# LCL.net
KiCad netlist of a schematic drawn in Altium Designer
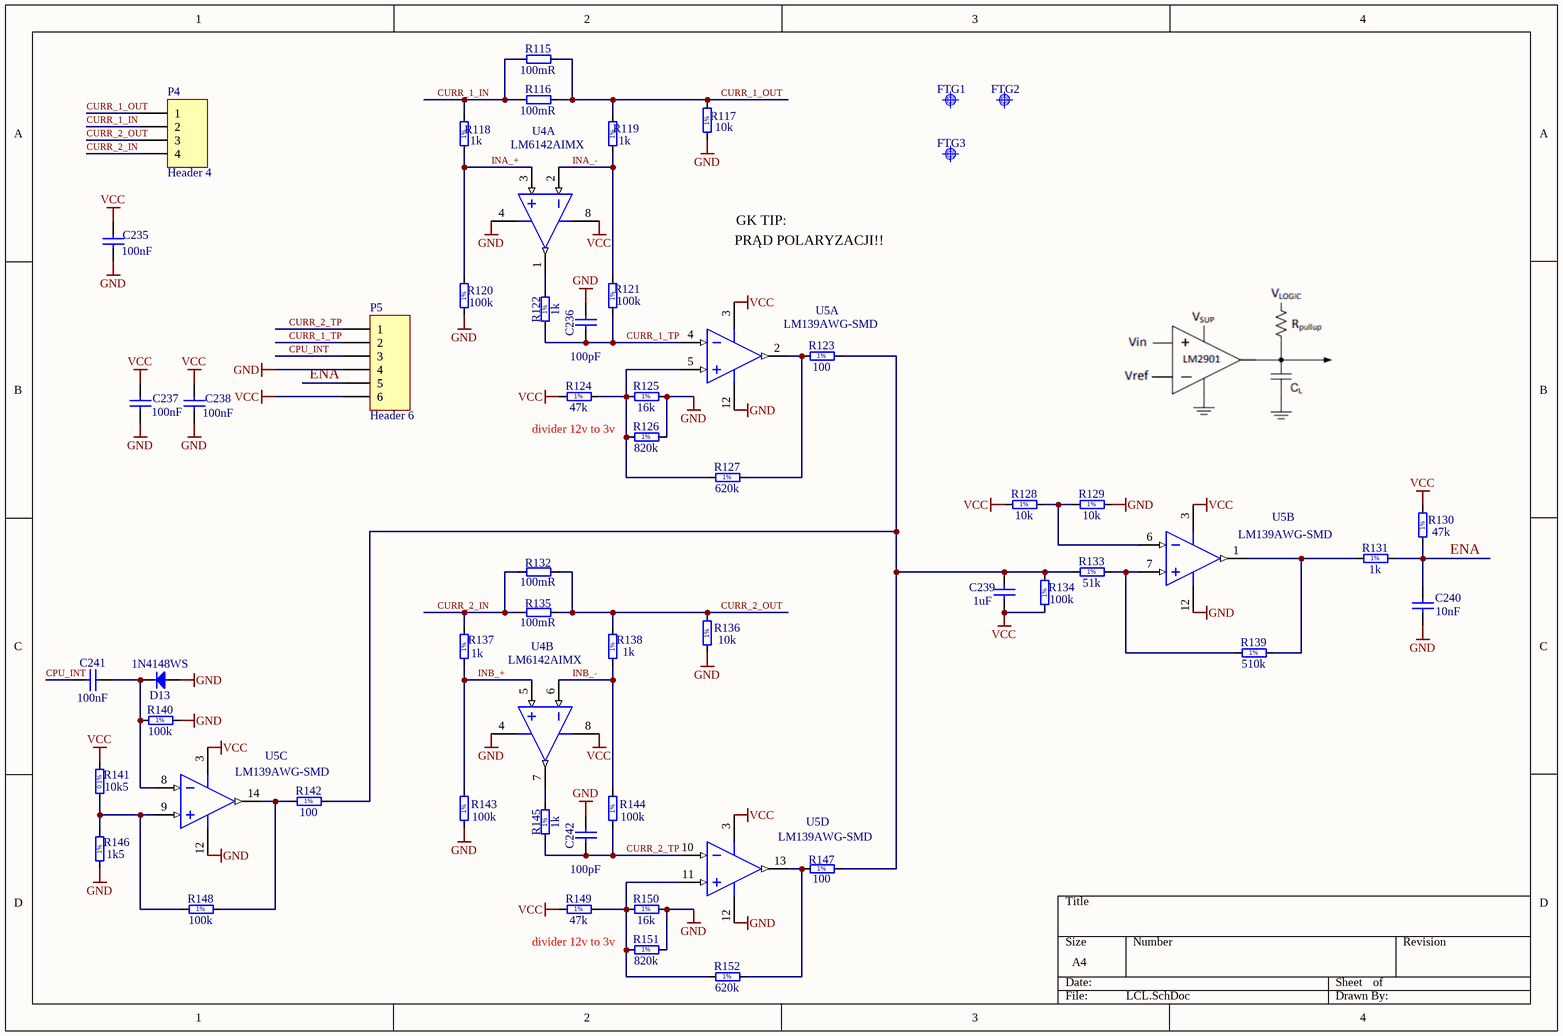
[diagram p0: LCL.SchDoc]

(export (version "E")
  (design (tool "Eeschema 10.0.6"))
  (components
    (comp (ref "C235")
      (value "100nF")
      (footprint "CAPC1608X87N")
      (description "Non-polarised capacitor")
      (fields
        (field (name "PART NUMBER") "CC0603_100NF_50V_10%_X7R")
        (field (name "VOLTAGE") "50V")
        (field (name "AUTHOR") "CERN DEM JLC")
      )
      (libsource (lib "Capacitors") (part "Capacitor - non polarized"))
    )
    (comp (ref "C236")
      (value "100pF")
      (footprint "CAPC1608X87N")
      (description "Non-polarised capacitor")
      (fields
        (field (name "PART NUMBER") "CC0603_100PF_50V_10%_X7R")
        (field (name "VOLTAGE") "50V")
        (field (name "AUTHOR") "CERN DEM JLC")
      )
      (libsource (lib "Capacitors") (part "Capacitor - non polarized"))
    )
    (comp (ref "C237")
      (value "100nF")
      (footprint "CAPC1608X87N")
      (description "Non-polarised capacitor")
      (fields
        (field (name "PART NUMBER") "CC0603_100NF_50V_10%_X7R")
        (field (name "VOLTAGE") "50V")
        (field (name "AUTHOR") "CERN DEM JLC")
      )
      (libsource (lib "Capacitors") (part "Capacitor - non polarized"))
    )
    (comp (ref "C238")
      (value "100nF")
      (footprint "CAPC1608X87N")
      (description "Non-polarised capacitor")
      (fields
        (field (name "PART NUMBER") "CC0603_100NF_50V_10%_X7R")
        (field (name "VOLTAGE") "50V")
        (field (name "AUTHOR") "CERN DEM JLC")
      )
      (libsource (lib "Capacitors") (part "Capacitor - non polarized"))
    )
    (comp (ref "C239")
      (value "1uF")
      (footprint "CAPC1608X87N")
      (description "Non-polarised capacitor")
      (fields
        (field (name "PART NUMBER") "CC0603_1UF_25V_10%_X7R")
        (field (name "VOLTAGE") "25V")
        (field (name "AUTHOR") "CERN DEM JLC")
      )
      (libsource (lib "Capacitors") (part "Capacitor - non polarized"))
    )
    (comp (ref "C240")
      (value "10nF")
      (footprint "CAPC1608X87N")
      (description "Non-polarised capacitor")
      (fields
        (field (name "PART NUMBER") "CC0603_10NF_50V_10%_X7R")
        (field (name "VOLTAGE") "50V")
        (field (name "AUTHOR") "CERN DEM JLC")
      )
      (libsource (lib "Capacitors") (part "Capacitor - non polarized"))
    )
    (comp (ref "C241")
      (value "100nF")
      (footprint "CAPC1608X87N")
      (description "Non-polarised capacitor")
      (fields
        (field (name "PART NUMBER") "CC0603_100NF_50V_10%_X7R")
        (field (name "VOLTAGE") "50V")
        (field (name "AUTHOR") "CERN DEM JLC")
      )
      (libsource (lib "Capacitors") (part "Capacitor - non polarized"))
    )
    (comp (ref "C242")
      (value "100pF")
      (footprint "CAPC1608X87N")
      (description "Non-polarised capacitor")
      (fields
        (field (name "PART NUMBER") "CC0603_100PF_50V_10%_X7R")
        (field (name "VOLTAGE") "50V")
        (field (name "AUTHOR") "CERN DEM JLC")
      )
      (libsource (lib "Capacitors") (part "Capacitor - non polarized"))
    )
    (comp (ref "D13")
      (value "1N4148WS")
      (footprint "SODFL2512X100N")
      (description "Diode")
      (fields
        (field (name "VOLTAGE") "75V")
        (field (name "POWER") "150mA")
        (field (name "AUTHOR") "CERN DEM JLC")
      )
      (libsource (lib "ICs And Semiconductors") (part "Diode"))
    )
    (comp (ref "FTG1")
      (value "Use only in PCB")
      (footprint "FIDUCIAL_TOP_C100-200")
      (description "Fiducial Target")
      (fields (field (name "PART NUMBER") "FIDUCIAL_TARGET_C100-200") (field (name "AUTHOR") "CERN DEM JLC"))
      (libsource (lib "Eletro-mechanical") (part "Fiducial Target"))
    )
    (comp (ref "FTG2")
      (value "Use only in PCB")
      (footprint "FIDUCIAL_TOP_C100-200")
      (description "Fiducial Target")
      (fields (field (name "PART NUMBER") "FIDUCIAL_TARGET_C100-200") (field (name "AUTHOR") "CERN DEM JLC"))
      (libsource (lib "Eletro-mechanical") (part "Fiducial Target"))
    )
    (comp (ref "FTG3")
      (value "Use only in PCB")
      (footprint "FIDUCIAL_TOP_C100-200")
      (description "Fiducial Target")
      (fields (field (name "PART NUMBER") "FIDUCIAL_TARGET_C100-200") (field (name "AUTHOR") "CERN DEM JLC"))
      (libsource (lib "Eletro-mechanical") (part "Fiducial Target"))
    )
    (comp (ref "P4")
      (value "Header 4")
      (footprint "1x4 Header 2mm male")
      (description "Header, 4-Pin")
      (fields (field (name "PUBLISHER") "Altium Limited"))
      (libsource (lib "Connectors-headers") (part "Header 4"))
    )
    (comp (ref "P5")
      (value "Header 6")
      (footprint "2x3 Header 2mm male")
      (description "Header, 6-Pin")
      (fields (field (name "PUBLISHER") "Altium Limited"))
      (libsource (lib "Connectors-headers") (part "Header 6"))
    )
    (comp (ref "R115")
      (value "100mR")
      (footprint "RESC1608X55N")
      (description "Resistor")
      (fields
        (field (name "PART NUMBER") "100mR 0603")
        (field (name "MANUFACTURER") "GENERIC")
        (field (name "AUTHOR") "CERN DEM JLC")
      )
      (libsource (lib "Resistors") (part "Resistor"))
    )
    (comp (ref "R116")
      (value "100mR")
      (footprint "RESC1608X55N")
      (description "Resistor")
      (fields
        (field (name "PART NUMBER") "100mR 0603")
        (field (name "MANUFACTURER") "GENERIC")
        (field (name "AUTHOR") "CERN DEM JLC")
      )
      (libsource (lib "Resistors") (part "Resistor"))
    )
    (comp (ref "R117")
      (value "10k")
      (footprint "RESC1608X55N")
      (description "Resistor - 1%")
      (fields
        (field (name "PART NUMBER") "R0603_10K_1%_0.1W_100PPM")
        (field (name "POWER") "0.1W")
        (field (name "AUTHOR") "CERN DEM JLC")
      )
      (libsource (lib "Resistors") (part "Resistor - 1%"))
    )
    (comp (ref "R118")
      (value "1k")
      (footprint "RESC1608X55N")
      (description "Resistor - 1%")
      (fields
        (field (name "PART NUMBER") "R0603_1K_1%_0.1W_100PPM")
        (field (name "POWER") "0.1W")
        (field (name "AUTHOR") "CERN DEM JLC")
      )
      (libsource (lib "Resistors") (part "Resistor - 1%"))
    )
    (comp (ref "R119")
      (value "1k")
      (footprint "RESC1608X55N")
      (description "Resistor - 1%")
      (fields
        (field (name "PART NUMBER") "R0603_1K_1%_0.1W_100PPM")
        (field (name "POWER") "0.1W")
        (field (name "AUTHOR") "CERN DEM JLC")
      )
      (libsource (lib "Resistors") (part "Resistor - 1%"))
    )
    (comp (ref "R120")
      (value "100k")
      (footprint "RESC1608X55N")
      (description "Resistor - 1%")
      (fields
        (field (name "PART NUMBER") "R0603_100K_1%_0.1W_100PPM")
        (field (name "POWER") "0.1W")
        (field (name "AUTHOR") "CERN DEM JLC")
      )
      (libsource (lib "Resistors") (part "Resistor - 1%"))
    )
    (comp (ref "R121")
      (value "100k")
      (footprint "RESC1608X55N")
      (description "Resistor - 1%")
      (fields
        (field (name "PART NUMBER") "R0603_100K_1%_0.1W_100PPM")
        (field (name "POWER") "0.1W")
        (field (name "AUTHOR") "CERN DEM JLC")
      )
      (libsource (lib "Resistors") (part "Resistor - 1%"))
    )
    (comp (ref "R122")
      (value "1k")
      (footprint "RESC1608X55N")
      (description "Resistor - 1%")
      (fields
        (field (name "PART NUMBER") "R0603_1K_1%_0.1W_100PPM")
        (field (name "POWER") "0.1W")
        (field (name "AUTHOR") "CERN DEM JLC")
      )
      (libsource (lib "Resistors") (part "Resistor - 1%"))
    )
    (comp (ref "R123")
      (value "100")
      (footprint "RESC1608X55N")
      (description "Resistor - 1%")
      (fields
        (field (name "PART NUMBER") "R0603_100R_1%_0.1W_100PPM")
        (field (name "POWER") "0.1W")
        (field (name "AUTHOR") "CERN DEM JLC")
      )
      (libsource (lib "Resistors") (part "Resistor - 1%"))
    )
    (comp (ref "R124")
      (value "47k")
      (footprint "RESC1608X55N")
      (description "Resistor - 1%")
      (fields
        (field (name "PART NUMBER") "R0603_47K_1%_0.1W_100PPM")
        (field (name "POWER") "0.1W")
        (field (name "AUTHOR") "CERN DEM JLC")
      )
      (libsource (lib "Resistors") (part "Resistor - 1%"))
    )
    (comp (ref "R125")
      (value "16k")
      (footprint "RESC1608X55N")
      (description "Resistor - 1%")
      (fields
        (field (name "PART NUMBER") "R0603_16K_1%_0.1W_100PPM")
        (field (name "POWER") "0.1W")
        (field (name "AUTHOR") "CERN DEM JLC")
      )
      (libsource (lib "Resistors") (part "Resistor - 1%"))
    )
    (comp (ref "R126")
      (value "820k")
      (footprint "RESC1608X55N")
      (description "Resistor - 1%")
      (fields
        (field (name "PART NUMBER") "R0603_820K_1%_0.1W_100PPM")
        (field (name "POWER") "0.1W")
        (field (name "AUTHOR") "CERN DEM JLC")
      )
      (libsource (lib "Resistors") (part "Resistor - 1%"))
    )
    (comp (ref "R127")
      (value "620k")
      (footprint "RESC1608X55N")
      (description "Resistor - 1%")
      (fields
        (field (name "PART NUMBER") "R0603_620K_1%_0.1W_100PPM")
        (field (name "POWER") "0.1W")
        (field (name "AUTHOR") "CERN DEM JLC")
      )
      (libsource (lib "Resistors") (part "Resistor - 1%"))
    )
    (comp (ref "R128")
      (value "10k")
      (footprint "RESC1608X55N")
      (description "Resistor - 1%")
      (fields
        (field (name "PART NUMBER") "R0603_10K_1%_0.1W_100PPM")
        (field (name "POWER") "0.1W")
        (field (name "AUTHOR") "CERN DEM JLC")
      )
      (libsource (lib "Resistors") (part "Resistor - 1%"))
    )
    (comp (ref "R129")
      (value "10k")
      (footprint "RESC1608X55N")
      (description "Resistor - 1%")
      (fields
        (field (name "PART NUMBER") "R0603_10K_1%_0.1W_100PPM")
        (field (name "POWER") "0.1W")
        (field (name "AUTHOR") "CERN DEM JLC")
      )
      (libsource (lib "Resistors") (part "Resistor - 1%"))
    )
    (comp (ref "R130")
      (value "47k")
      (footprint "RESC1608X55N")
      (description "Resistor - 1%")
      (fields
        (field (name "PART NUMBER") "R0603_47K_1%_0.1W_100PPM")
        (field (name "POWER") "0.1W")
        (field (name "AUTHOR") "CERN DEM JLC")
      )
      (libsource (lib "Resistors") (part "Resistor - 1%"))
    )
    (comp (ref "R131")
      (value "1k")
      (footprint "RESC1608X55N")
      (description "Resistor - 1%")
      (fields
        (field (name "PART NUMBER") "R0603_1K_1%_0.1W_100PPM")
        (field (name "POWER") "0.1W")
        (field (name "AUTHOR") "CERN DEM JLC")
      )
      (libsource (lib "Resistors") (part "Resistor - 1%"))
    )
    (comp (ref "R132")
      (value "100mR")
      (footprint "RESC1608X55N")
      (description "Resistor")
      (fields
        (field (name "PART NUMBER") "100mR 0603")
        (field (name "MANUFACTURER") "GENERIC")
        (field (name "AUTHOR") "CERN DEM JLC")
      )
      (libsource (lib "Resistors") (part "Resistor"))
    )
    (comp (ref "R133")
      (value "51k")
      (footprint "RESC1608X55N")
      (description "Resistor - 1%")
      (fields
        (field (name "PART NUMBER") "R0603_51K_1%_0.1W_100PPM")
        (field (name "POWER") "0.1W")
        (field (name "AUTHOR") "CERN DEM JLC")
      )
      (libsource (lib "Resistors") (part "Resistor - 1%"))
    )
    (comp (ref "R134")
      (value "100k")
      (footprint "RESC1608X55N")
      (description "Resistor - 1%")
      (fields
        (field (name "PART NUMBER") "R0603_100K_1%_0.1W_100PPM")
        (field (name "POWER") "0.1W")
        (field (name "AUTHOR") "CERN DEM JLC")
      )
      (libsource (lib "Resistors") (part "Resistor - 1%"))
    )
    (comp (ref "R135")
      (value "100mR")
      (footprint "RESC1608X55N")
      (description "Resistor")
      (fields
        (field (name "PART NUMBER") "100mR 0603")
        (field (name "MANUFACTURER") "GENERIC")
        (field (name "AUTHOR") "CERN DEM JLC")
      )
      (libsource (lib "Resistors") (part "Resistor"))
    )
    (comp (ref "R136")
      (value "10k")
      (footprint "RESC1608X55N")
      (description "Resistor - 1%")
      (fields
        (field (name "PART NUMBER") "R0603_10K_1%_0.1W_100PPM")
        (field (name "POWER") "0.1W")
        (field (name "AUTHOR") "CERN DEM JLC")
      )
      (libsource (lib "Resistors") (part "Resistor - 1%"))
    )
    (comp (ref "R137")
      (value "1k")
      (footprint "RESC1608X55N")
      (description "Resistor - 1%")
      (fields
        (field (name "PART NUMBER") "R0603_1K_1%_0.1W_100PPM")
        (field (name "POWER") "0.1W")
        (field (name "AUTHOR") "CERN DEM JLC")
      )
      (libsource (lib "Resistors") (part "Resistor - 1%"))
    )
    (comp (ref "R138")
      (value "1k")
      (footprint "RESC1608X55N")
      (description "Resistor - 1%")
      (fields
        (field (name "PART NUMBER") "R0603_1K_1%_0.1W_100PPM")
        (field (name "POWER") "0.1W")
        (field (name "AUTHOR") "CERN DEM JLC")
      )
      (libsource (lib "Resistors") (part "Resistor - 1%"))
    )
    (comp (ref "R139")
      (value "510k")
      (footprint "RESC1608X55N")
      (description "Resistor - 1%")
      (fields
        (field (name "PART NUMBER") "R0603_510K_1%_0.1W_100PPM")
        (field (name "POWER") "0.1W")
        (field (name "AUTHOR") "CERN DEM JLC")
      )
      (libsource (lib "Resistors") (part "Resistor - 1%"))
    )
    (comp (ref "R140")
      (value "100k")
      (footprint "RESC1608X55N")
      (description "Resistor - 1%")
      (fields
        (field (name "PART NUMBER") "R0603_100K_1%_0.1W_100PPM")
        (field (name "POWER") "0.1W")
        (field (name "AUTHOR") "CERN DEM JLC")
      )
      (libsource (lib "Resistors") (part "Resistor - 1%"))
    )
    (comp (ref "R141")
      (value "10k5")
      (footprint "RESC1608X55N")
      (description "Resistor - 0.1%")
      (fields
        (field (name "PART NUMBER") "R0603_10K5_0.1%_0.063W_10PPM")
        (field (name "POWER") "0.063W")
        (field (name "AUTHOR") "CERN DEM JLC")
      )
      (libsource (lib "Resistors") (part "Resistor - 0.1%"))
    )
    (comp (ref "R142")
      (value "100")
      (footprint "RESC1608X55N")
      (description "Resistor - 1%")
      (fields
        (field (name "PART NUMBER") "R0603_100R_1%_0.1W_100PPM")
        (field (name "POWER") "0.1W")
        (field (name "AUTHOR") "CERN DEM JLC")
      )
      (libsource (lib "Resistors") (part "Resistor - 1%"))
    )
    (comp (ref "R143")
      (value "100k")
      (footprint "RESC1608X55N")
      (description "Resistor - 1%")
      (fields
        (field (name "PART NUMBER") "R0603_100K_1%_0.1W_100PPM")
        (field (name "POWER") "0.1W")
        (field (name "AUTHOR") "CERN DEM JLC")
      )
      (libsource (lib "Resistors") (part "Resistor - 1%"))
    )
    (comp (ref "R144")
      (value "100k")
      (footprint "RESC1608X55N")
      (description "Resistor - 1%")
      (fields
        (field (name "PART NUMBER") "R0603_100K_1%_0.1W_100PPM")
        (field (name "POWER") "0.1W")
        (field (name "AUTHOR") "CERN DEM JLC")
      )
      (libsource (lib "Resistors") (part "Resistor - 1%"))
    )
    (comp (ref "R145")
      (value "1k")
      (footprint "RESC1608X55N")
      (description "Resistor - 1%")
      (fields
        (field (name "PART NUMBER") "R0603_1K_1%_0.1W_100PPM")
        (field (name "POWER") "0.1W")
        (field (name "AUTHOR") "CERN DEM JLC")
      )
      (libsource (lib "Resistors") (part "Resistor - 1%"))
    )
    (comp (ref "R146")
      (value "1k5")
      (footprint "RESC1608X55N")
      (description "Resistor - 1%")
      (fields
        (field (name "PART NUMBER") "R0603_1K5_1%_0.1W_100PPM")
        (field (name "POWER") "0.1W")
        (field (name "AUTHOR") "CERN DEM JLC")
      )
      (libsource (lib "Resistors") (part "Resistor - 1%"))
    )
    (comp (ref "R147")
      (value "100")
      (footprint "RESC1608X55N")
      (description "Resistor - 1%")
      (fields
        (field (name "PART NUMBER") "R0603_100R_1%_0.1W_100PPM")
        (field (name "POWER") "0.1W")
        (field (name "AUTHOR") "CERN DEM JLC")
      )
      (libsource (lib "Resistors") (part "Resistor - 1%"))
    )
    (comp (ref "R148")
      (value "100k")
      (footprint "RESC1608X55N")
      (description "Resistor - 1%")
      (fields
        (field (name "PART NUMBER") "R0603_100K_1%_0.1W_100PPM")
        (field (name "POWER") "0.1W")
        (field (name "AUTHOR") "CERN DEM JLC")
      )
      (libsource (lib "Resistors") (part "Resistor - 1%"))
    )
    (comp (ref "R149")
      (value "47k")
      (footprint "RESC1608X55N")
      (description "Resistor - 1%")
      (fields
        (field (name "PART NUMBER") "R0603_47K_1%_0.1W_100PPM")
        (field (name "POWER") "0.1W")
        (field (name "AUTHOR") "CERN DEM JLC")
      )
      (libsource (lib "Resistors") (part "Resistor - 1%"))
    )
    (comp (ref "R150")
      (value "16k")
      (footprint "RESC1608X55N")
      (description "Resistor - 1%")
      (fields
        (field (name "PART NUMBER") "R0603_16K_1%_0.1W_100PPM")
        (field (name "POWER") "0.1W")
        (field (name "AUTHOR") "CERN DEM JLC")
      )
      (libsource (lib "Resistors") (part "Resistor - 1%"))
    )
    (comp (ref "R151")
      (value "820k")
      (footprint "RESC1608X55N")
      (description "Resistor - 1%")
      (fields
        (field (name "PART NUMBER") "R0603_820K_1%_0.1W_100PPM")
        (field (name "POWER") "0.1W")
        (field (name "AUTHOR") "CERN DEM JLC")
      )
      (libsource (lib "Resistors") (part "Resistor - 1%"))
    )
    (comp (ref "R152")
      (value "620k")
      (footprint "RESC1608X55N")
      (description "Resistor - 1%")
      (fields
        (field (name "PART NUMBER") "R0603_620K_1%_0.1W_100PPM")
        (field (name "POWER") "0.1W")
        (field (name "AUTHOR") "CERN DEM JLC")
      )
      (libsource (lib "Resistors") (part "Resistor - 1%"))
    )
    (comp (ref "U4")
      (value "LM6142AIMX")
      (footprint "M08A_N")
      (description "Dual High Speed/Low Power 17 MHz Rail-to-Rail I/O Operational Amplifier, 8-pin Narrow SOIC")
      (fields (field (name "MANUFACTURER") "National Semiconductor"))
      (libsource (lib "National Semiconductor Amplifier") (part "LM6142AIMX"))
    )
    (comp (ref "U5")
      (value "LM139AWG-SMD")
      (footprint "WG14A_N")
      (description "Low Power Low Offset Voltage Quad Comparator, 14-pin CerPACK")
      (fields (field (name "MANUFACTURER") "National Semiconductor"))
      (libsource (lib "National Semiconductor Amplifier") (part "LM139AWG-SMD"))
    )
  )
  (nets
    (net (code "1") (name "/CPU_INT") (class "Default")
      (node (ref "C241") (pin "1") (pinfunction "1_1") (pintype "passive"))
      (node (ref "P5") (pin "3") (pinfunction "3_3") (pintype "passive"))
    )
    (net (code "2") (name "/CURR_1_IN") (class "Default")
      (node (ref "P4") (pin "2") (pinfunction "2_2") (pintype "passive"))
      (node (ref "R115") (pin "1") (pinfunction "1_1") (pintype "passive"))
      (node (ref "R116") (pin "1") (pinfunction "1_1") (pintype "passive"))
      (node (ref "R118") (pin "2") (pinfunction "2_2") (pintype "passive"))
    )
    (net (code "3") (name "/CURR_1_OUT") (class "Default")
      (node (ref "P4") (pin "1") (pinfunction "1_1") (pintype "passive"))
      (node (ref "R115") (pin "2") (pinfunction "2_2") (pintype "passive"))
      (node (ref "R116") (pin "2") (pinfunction "2_2") (pintype "passive"))
      (node (ref "R117") (pin "2") (pinfunction "2_2") (pintype "passive"))
      (node (ref "R119") (pin "2") (pinfunction "2_2") (pintype "passive"))
    )
    (net (code "4") (name "/CURR_1_TP") (class "Default")
      (node (ref "C236") (pin "1") (pinfunction "1_1") (pintype "passive"))
      (node (ref "P5") (pin "2") (pinfunction "2_2") (pintype "passive"))
      (node (ref "R121") (pin "1") (pinfunction "1_1") (pintype "passive"))
      (node (ref "R122") (pin "1") (pinfunction "1_1") (pintype "passive"))
      (node (ref "U5") (pin "4") (pinfunction "IN1-_4") (pintype "input"))
    )
    (net (code "5") (name "/CURR_2_IN") (class "Default")
      (node (ref "P4") (pin "4") (pinfunction "4_4") (pintype "passive"))
      (node (ref "R132") (pin "1") (pinfunction "1_1") (pintype "passive"))
      (node (ref "R135") (pin "1") (pinfunction "1_1") (pintype "passive"))
      (node (ref "R137") (pin "2") (pinfunction "2_2") (pintype "passive"))
    )
    (net (code "6") (name "/CURR_2_OUT") (class "Default")
      (node (ref "P4") (pin "3") (pinfunction "3_3") (pintype "passive"))
      (node (ref "R132") (pin "2") (pinfunction "2_2") (pintype "passive"))
      (node (ref "R135") (pin "2") (pinfunction "2_2") (pintype "passive"))
      (node (ref "R136") (pin "2") (pinfunction "2_2") (pintype "passive"))
      (node (ref "R138") (pin "2") (pinfunction "2_2") (pintype "passive"))
    )
    (net (code "7") (name "/CURR_2_TP") (class "Default")
      (node (ref "C242") (pin "1") (pinfunction "1_1") (pintype "passive"))
      (node (ref "P5") (pin "1") (pinfunction "1_1") (pintype "passive"))
      (node (ref "R144") (pin "1") (pinfunction "1_1") (pintype "passive"))
      (node (ref "R145") (pin "1") (pinfunction "1_1") (pintype "passive"))
      (node (ref "U5") (pin "10") (pinfunction "IN4-_10") (pintype "input"))
    )
    (net (code "8") (name "/ENA") (class "Default")
      (node (ref "C240") (pin "2") (pinfunction "2_2") (pintype "passive"))
      (node (ref "P5") (pin "5") (pinfunction "5_5") (pintype "passive"))
      (node (ref "R130") (pin "1") (pinfunction "1_1") (pintype "passive"))
      (node (ref "R131") (pin "2") (pinfunction "2_2") (pintype "passive"))
    )
    (net (code "9") (name "/INA_+") (class "Default")
      (node (ref "R118") (pin "1") (pinfunction "1_1") (pintype "passive"))
      (node (ref "R120") (pin "2") (pinfunction "2_2") (pintype "passive"))
      (node (ref "U4") (pin "3") (pinfunction "INA+_3") (pintype "input"))
    )
    (net (code "10") (name "/INA_-") (class "Default")
      (node (ref "R119") (pin "1") (pinfunction "1_1") (pintype "passive"))
      (node (ref "R121") (pin "2") (pinfunction "2_2") (pintype "passive"))
      (node (ref "U4") (pin "2") (pinfunction "INA-_2") (pintype "input"))
    )
    (net (code "11") (name "/INB_+") (class "Default")
      (node (ref "R137") (pin "1") (pinfunction "1_1") (pintype "passive"))
      (node (ref "R143") (pin "2") (pinfunction "2_2") (pintype "passive"))
      (node (ref "U4") (pin "5") (pinfunction "INB+_5") (pintype "input"))
    )
    (net (code "12") (name "/INB_-") (class "Default")
      (node (ref "R138") (pin "1") (pinfunction "1_1") (pintype "passive"))
      (node (ref "R144") (pin "2") (pinfunction "2_2") (pintype "passive"))
      (node (ref "U4") (pin "6") (pinfunction "INB-_6") (pintype "input"))
    )
    (net (code "13") (name "GND") (class "Default")
      (node (ref "C235") (pin "1") (pinfunction "1_1") (pintype "passive"))
      (node (ref "C236") (pin "2") (pinfunction "2_2") (pintype "passive"))
      (node (ref "C237") (pin "1") (pinfunction "1_1") (pintype "passive"))
      (node (ref "C238") (pin "1") (pinfunction "1_1") (pintype "passive"))
      (node (ref "C240") (pin "1") (pinfunction "1_1") (pintype "passive"))
      (node (ref "C242") (pin "2") (pinfunction "2_2") (pintype "passive"))
      (node (ref "D13") (pin "2") (pinfunction "A_2") (pintype "passive"))
      (node (ref "P5") (pin "4") (pinfunction "4_4") (pintype "passive"))
      (node (ref "R117") (pin "1") (pinfunction "1_1") (pintype "passive"))
      (node (ref "R120") (pin "1") (pinfunction "1_1") (pintype "passive"))
      (node (ref "R125") (pin "2") (pinfunction "2_2") (pintype "passive"))
      (node (ref "R126") (pin "2") (pinfunction "2_2") (pintype "passive"))
      (node (ref "R129") (pin "2") (pinfunction "2_2") (pintype "passive"))
      (node (ref "R136") (pin "1") (pinfunction "1_1") (pintype "passive"))
      (node (ref "R140") (pin "2") (pinfunction "2_2") (pintype "passive"))
      (node (ref "R143") (pin "1") (pinfunction "1_1") (pintype "passive"))
      (node (ref "R146") (pin "1") (pinfunction "1_1") (pintype "passive"))
      (node (ref "R150") (pin "2") (pinfunction "2_2") (pintype "passive"))
      (node (ref "R151") (pin "2") (pinfunction "2_2") (pintype "passive"))
      (node (ref "U4") (pin "4") (pinfunction "V-_4") (pintype "power_in"))
      (node (ref "U5") (pin "12") (pinfunction "GND_12") (pintype "power_in"))
    )
    (net (code "14") (name "Net-(C239-Pad2)") (class "Default")
      (node (ref "C239") (pin "2") (pinfunction "2_2") (pintype "passive"))
      (node (ref "R123") (pin "2") (pinfunction "2_2") (pintype "passive"))
      (node (ref "R133") (pin "1") (pinfunction "1_1") (pintype "passive"))
      (node (ref "R134") (pin "2") (pinfunction "2_2") (pintype "passive"))
      (node (ref "R142") (pin "2") (pinfunction "2_2") (pintype "passive"))
      (node (ref "R147") (pin "2") (pinfunction "2_2") (pintype "passive"))
    )
    (net (code "15") (name "Net-(D13-C)") (class "Default")
      (node (ref "C241") (pin "2") (pinfunction "2_2") (pintype "passive"))
      (node (ref "D13") (pin "1") (pinfunction "C_1") (pintype "passive"))
      (node (ref "R140") (pin "1") (pinfunction "1_1") (pintype "passive"))
      (node (ref "U5") (pin "8") (pinfunction "IN3-_8") (pintype "input"))
    )
    (net (code "16") (name "Net-(U4A-OUTA)") (class "Default")
      (node (ref "R122") (pin "2") (pinfunction "2_2") (pintype "passive"))
      (node (ref "U4") (pin "1") (pinfunction "OUTA_1") (pintype "output"))
    )
    (net (code "17") (name "Net-(U4B-OUTB)") (class "Default")
      (node (ref "R145") (pin "2") (pinfunction "2_2") (pintype "passive"))
      (node (ref "U4") (pin "7") (pinfunction "OUTB_7") (pintype "output"))
    )
    (net (code "18") (name "Net-(U5A-IN1+)") (class "Default")
      (node (ref "R124") (pin "2") (pinfunction "2_2") (pintype "passive"))
      (node (ref "R125") (pin "1") (pinfunction "1_1") (pintype "passive"))
      (node (ref "R126") (pin "1") (pinfunction "1_1") (pintype "passive"))
      (node (ref "R127") (pin "1") (pinfunction "1_1") (pintype "passive"))
      (node (ref "U5") (pin "5") (pinfunction "IN1+_5") (pintype "input"))
    )
    (net (code "19") (name "Net-(U5A-OUT1)") (class "Default")
      (node (ref "R123") (pin "1") (pinfunction "1_1") (pintype "passive"))
      (node (ref "R127") (pin "2") (pinfunction "2_2") (pintype "passive"))
      (node (ref "U5") (pin "2") (pinfunction "OUT1_2") (pintype "output"))
    )
    (net (code "20") (name "Net-(U5B-IN2+)") (class "Default")
      (node (ref "R133") (pin "2") (pinfunction "2_2") (pintype "passive"))
      (node (ref "R139") (pin "1") (pinfunction "1_1") (pintype "passive"))
      (node (ref "U5") (pin "7") (pinfunction "IN2+_7") (pintype "input"))
    )
    (net (code "21") (name "Net-(U5B-IN2-)") (class "Default")
      (node (ref "R128") (pin "2") (pinfunction "2_2") (pintype "passive"))
      (node (ref "R129") (pin "1") (pinfunction "1_1") (pintype "passive"))
      (node (ref "U5") (pin "6") (pinfunction "IN2-_6") (pintype "input"))
    )
    (net (code "22") (name "Net-(U5B-OUT2)") (class "Default")
      (node (ref "R131") (pin "1") (pinfunction "1_1") (pintype "passive"))
      (node (ref "R139") (pin "2") (pinfunction "2_2") (pintype "passive"))
      (node (ref "U5") (pin "1") (pinfunction "OUT2_1") (pintype "output"))
    )
    (net (code "23") (name "Net-(U5C-IN3+)") (class "Default")
      (node (ref "R141") (pin "1") (pinfunction "1_1") (pintype "passive"))
      (node (ref "R146") (pin "2") (pinfunction "2_2") (pintype "passive"))
      (node (ref "R148") (pin "1") (pinfunction "1_1") (pintype "passive"))
      (node (ref "U5") (pin "9") (pinfunction "IN3+_9") (pintype "input"))
    )
    (net (code "24") (name "Net-(U5C-OUT3)") (class "Default")
      (node (ref "R142") (pin "1") (pinfunction "1_1") (pintype "passive"))
      (node (ref "R148") (pin "2") (pinfunction "2_2") (pintype "passive"))
      (node (ref "U5") (pin "14") (pinfunction "OUT3_14") (pintype "output"))
    )
    (net (code "25") (name "Net-(U5D-IN4+)") (class "Default")
      (node (ref "R149") (pin "2") (pinfunction "2_2") (pintype "passive"))
      (node (ref "R150") (pin "1") (pinfunction "1_1") (pintype "passive"))
      (node (ref "R151") (pin "1") (pinfunction "1_1") (pintype "passive"))
      (node (ref "R152") (pin "1") (pinfunction "1_1") (pintype "passive"))
      (node (ref "U5") (pin "11") (pinfunction "IN4+_11") (pintype "input"))
    )
    (net (code "26") (name "Net-(U5D-OUT4)") (class "Default")
      (node (ref "R147") (pin "1") (pinfunction "1_1") (pintype "passive"))
      (node (ref "R152") (pin "2") (pinfunction "2_2") (pintype "passive"))
      (node (ref "U5") (pin "13") (pinfunction "OUT4_13") (pintype "output"))
    )
    (net (code "27") (name "VCC") (class "Default")
      (node (ref "C235") (pin "2") (pinfunction "2_2") (pintype "passive"))
      (node (ref "C237") (pin "2") (pinfunction "2_2") (pintype "passive"))
      (node (ref "C238") (pin "2") (pinfunction "2_2") (pintype "passive"))
      (node (ref "C239") (pin "1") (pinfunction "1_1") (pintype "passive"))
      (node (ref "P5") (pin "6") (pinfunction "6_6") (pintype "passive"))
      (node (ref "R124") (pin "1") (pinfunction "1_1") (pintype "passive"))
      (node (ref "R128") (pin "1") (pinfunction "1_1") (pintype "passive"))
      (node (ref "R130") (pin "2") (pinfunction "2_2") (pintype "passive"))
      (node (ref "R134") (pin "1") (pinfunction "1_1") (pintype "passive"))
      (node (ref "R141") (pin "2") (pinfunction "2_2") (pintype "passive"))
      (node (ref "R149") (pin "1") (pinfunction "1_1") (pintype "passive"))
      (node (ref "U4") (pin "8") (pinfunction "V+_8") (pintype "power_in"))
      (node (ref "U5") (pin "3") (pinfunction "V+_3") (pintype "power_in"))
    )
  )
)
